# SAMV71_Xplained_Ultra_Power_Converter.net
KiCad netlist of a schematic drawn in Altium Designer
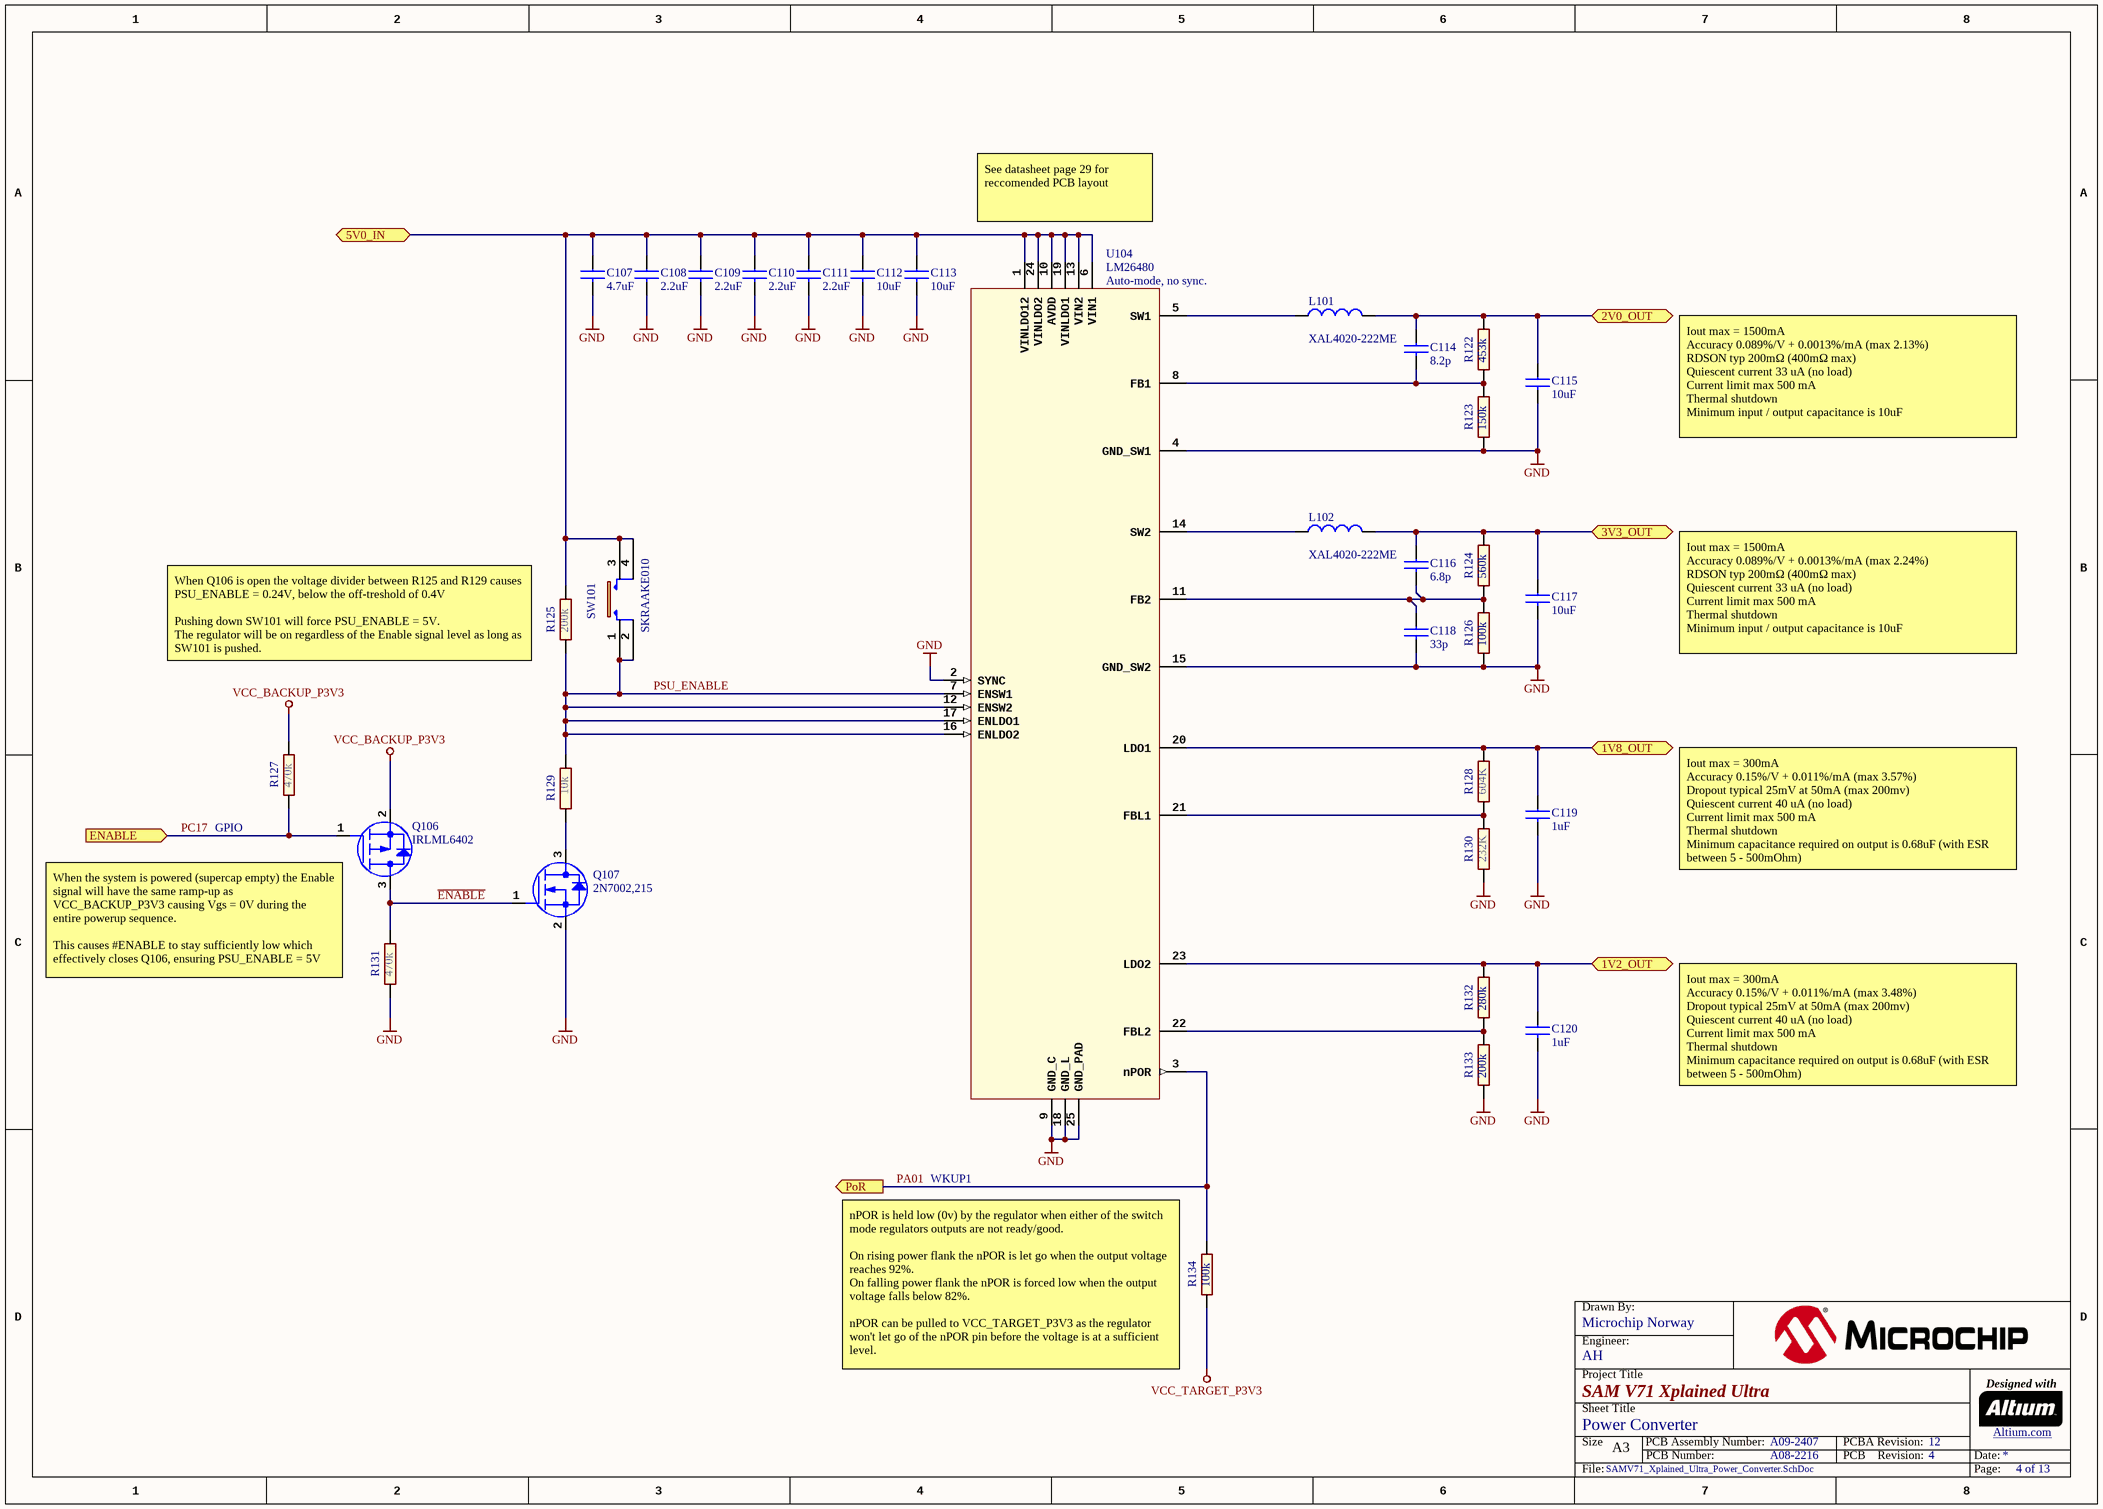
[diagram p0: SAMV71_Xplained_Ultra_Power_Converter.SchDoc]

(export (version "E")
  (design (tool "Eeschema 10.0.6"))
  (components
    (comp (ref "C107")
      (value "4.7uF")
      (footprint "AP1-00039")
      (description "Ceramic capacitor, SMD 0603, X5R, 10V, 10% (de31036)")
      (fields (field (name "TOLERANCE") "10%") (field (name "MANUFACTURER") "WALSIN Technology Corporation"))
      (libsource (lib "AltiumDbLib") (part "CAP-NONPOL"))
    )
    (comp (ref "C108")
      (value "2.2uF")
      (footprint "AP1-00053")
      (description "Ceramic capacitor, SMD 0402, X5R, 6.3V, +/-20%")
      (fields (field (name "TOLERANCE") "Â±20%") (field (name "MANUFACTURER") "Kemet"))
      (libsource (lib "AltiumDbLib") (part "CAP-NONPOL"))
    )
    (comp (ref "C109")
      (value "2.2uF")
      (footprint "AP1-00053")
      (description "Ceramic capacitor, SMD 0402, X5R, 6.3V, +/-20%")
      (fields (field (name "TOLERANCE") "Â±20%") (field (name "MANUFACTURER") "Kemet"))
      (libsource (lib "AltiumDbLib") (part "CAP-NONPOL"))
    )
    (comp (ref "C110")
      (value "2.2uF")
      (footprint "AP1-00053")
      (description "Ceramic capacitor, SMD 0402, X5R, 6.3V, +/-20%")
      (fields (field (name "TOLERANCE") "Â±20%") (field (name "MANUFACTURER") "Kemet"))
      (libsource (lib "AltiumDbLib") (part "CAP-NONPOL"))
    )
    (comp (ref "C111")
      (value "2.2uF")
      (footprint "AP1-00053")
      (description "Ceramic capacitor, SMD 0402, X5R, 6.3V, +/-20%")
      (fields (field (name "TOLERANCE") "Â±20%") (field (name "MANUFACTURER") "Kemet"))
      (libsource (lib "AltiumDbLib") (part "CAP-NONPOL"))
    )
    (comp (ref "C112")
      (value "10uF")
      (footprint "AP1-00041")
      (description "Ceramic capacitor, SMD 0805, X5R, 10V, 10 %, (de19441)")
      (fields (field (name "TOLERANCE") "10%") (field (name "MANUFACTURER") "Murata"))
      (libsource (lib "AltiumDbLib") (part "CAP-NONPOL"))
    )
    (comp (ref "C113")
      (value "10uF")
      (footprint "AP1-00041")
      (description "Ceramic capacitor, SMD 0805, X5R, 10V, 10 %, (de19441)")
      (fields (field (name "TOLERANCE") "10%") (field (name "MANUFACTURER") "Murata"))
      (libsource (lib "AltiumDbLib") (part "CAP-NONPOL"))
    )
    (comp (ref "C114")
      (value "8.2p")
      (footprint "AP1-00053")
      (description "Ceramic capacitor, SMD 0402, NP0, 50V, +/-5%")
      (fields (field (name "TOLERANCE") "50V, +/-5%") (field (name "MANUFACTURER") "YAGEO CORP"))
      (libsource (lib "AltiumDbLib") (part "CAP-NONPOL"))
    )
    (comp (ref "C115")
      (value "10uF")
      (footprint "AP1-00041")
      (description "Ceramic capacitor, SMD 0805, X5R, 10V, 10 %, (de19441)")
      (fields (field (name "TOLERANCE") "10%") (field (name "MANUFACTURER") "Murata"))
      (libsource (lib "AltiumDbLib") (part "CAP-NONPOL"))
    )
    (comp (ref "C116")
      (value "6.8p")
      (footprint "AP1-00053")
      (description "Ceramic capacitor, SMD 0402, NP0, 50V, +/-5%")
      (fields (field (name "TOLERANCE") "50V, +/-5%") (field (name "MANUFACTURER") "YAGEO CORP"))
      (libsource (lib "AltiumDbLib") (part "CAP-NONPOL"))
    )
    (comp (ref "C117")
      (value "10uF")
      (footprint "AP1-00041")
      (description "Ceramic capacitor, SMD 0805, X5R, 10V, 10 %, (de19441)")
      (fields (field (name "TOLERANCE") "10%") (field (name "MANUFACTURER") "Murata"))
      (libsource (lib "AltiumDbLib") (part "CAP-NONPOL"))
    )
    (comp (ref "C118")
      (value "33p")
      (footprint "AP1-00053")
      (description "Ceramic capacitor, SMD 0402, NP0, 50V, +/-5%")
      (fields (field (name "TOLERANCE") "50V, +/-5%") (field (name "MANUFACTURER") "Murata"))
      (libsource (lib "AltiumDbLib") (part "CAP-NONPOL"))
    )
    (comp (ref "C119")
      (value "1uF")
      (footprint "AP1-00053")
      (description "Ceramic capacitor, SMD 0402, X5R, 10V, ±10 %")
      (fields (field (name "MANUFACTURER") "AVX") (field (name "MPN") "0402ZD105KAT2A"))
      (libsource (lib "AltiumDbLib") (part "CAP-NONPOL"))
    )
    (comp (ref "C120")
      (value "1uF")
      (footprint "AP1-00053")
      (description "Ceramic capacitor, SMD 0402, X5R, 10V, ±10 %")
      (fields (field (name "MANUFACTURER") "AVX") (field (name "MPN") "0402ZD105KAT2A"))
      (libsource (lib "AltiumDbLib") (part "CAP-NONPOL"))
    )
    (comp (ref "L101")
      (value "XAL4020-222ME")
      (footprint "AP3-00119")
      (description "2.2ÂµH Shielded Power Inductor, 4x4x2mm, Isat=5.6A , Irms=4.0A , DCR=35.2mÎ©")
      (fields (field (name "TOLERANCE") "20%") (field (name "MANUFACTURER") "Coilcraft"))
      (libsource (lib "AltiumDbLib") (part "INDUCTOR"))
    )
    (comp (ref "L102")
      (value "XAL4020-222ME")
      (footprint "AP3-00119")
      (description "2.2ÂµH Shielded Power Inductor, 4x4x2mm, Isat=5.6A , Irms=4.0A , DCR=35.2mÎ©")
      (fields (field (name "TOLERANCE") "20%") (field (name "MANUFACTURER") "Coilcraft"))
      (libsource (lib "AltiumDbLib") (part "INDUCTOR"))
    )
    (comp (ref "Q106")
      (value "IRLML6402")
      (footprint "AP5-00002")
      (description "P-ch. MOSFET. -30V, -3.7A continuous,RDS(ON)=0.05Ohm@VGS=-4,5V, RDS(ON)=0.08Ohm@VGS=-2.5V")
      (fields (field (name "MANUFACTURER") "International Rectifier") (field (name "MPN") "IRLML6402PBF"))
      (libsource (lib "AltiumDbLib") (part "MOSFET_P_GSD"))
    )
    (comp (ref "Q107")
      (value "2N7002,215")
      (footprint "AP5-00002")
      (description "N-Channel MOSFET. 60V, 0.300A continuous, 1.2A Peak. RDS(ON) = 3.8Ohm@VGS=4.5V, VGS(th)<2.5V")
      (fields (field (name "MANUFACTURER") "NXP"))
      (libsource (lib "AltiumDbLib") (part "MOSFET_N_GSD"))
    )
    (comp (ref "R122")
      (value "453k")
      (footprint "AP2-00011")
      (description "Thick film resistor, SMD 0402, 1/16W, 1%")
      (fields (field (name "TOLERANCE") "1 %"))
      (libsource (lib "AltiumDbLib") (part "R2"))
    )
    (comp (ref "R123")
      (value "150k")
      (footprint "AP2-00011")
      (description "Thick film resistor, SMD 0402, 1/16W, 1%")
      (fields (field (name "TOLERANCE") "1 %") (field (name "MANUFACTURER") "ASJ"))
      (libsource (lib "AltiumDbLib") (part "R2"))
    )
    (comp (ref "R124")
      (value "560k")
      (footprint "AP2-00011")
      (description "Thick film resistor, SMD 0402, 1/16W, 1%")
      (fields (field (name "TOLERANCE") "1 %"))
      (libsource (lib "AltiumDbLib") (part "R2"))
    )
    (comp (ref "R125")
      (value "200k")
      (footprint "AP2-00011")
      (description "Thick film resistor, SMD 0402, 1/16W, 1%")
      (fields (field (name "TOLERANCE") "1 %") (field (name "MANUFACTURER") "ASJ"))
      (libsource (lib "AltiumDbLib") (part "R2"))
    )
    (comp (ref "R126")
      (value "100k")
      (footprint "AP2-00011")
      (description "Thick film resistor, SMD 0402, 1/16W, 1%")
      (fields (field (name "TOLERANCE") "1 %") (field (name "MANUFACTURER") "ASJ"))
      (libsource (lib "") (part "R2_1"))
    )
    (comp (ref "R127")
      (value "470k")
      (footprint "AP2-00011")
      (description "Thick film resistor, SMD 0402, 1/16W, 1%")
      (fields (field (name "TOLERANCE") "1 %") (field (name "MANUFACTURER") "ASJ"))
      (libsource (lib "AltiumDbLib") (part "R2"))
    )
    (comp (ref "R128")
      (value "604K")
      (footprint "AP2-00011")
      (description "Thick film resistor, SMD 0402, 1/16W, 1%")
      (fields (field (name "TOLERANCE") "1 %"))
      (libsource (lib "AltiumDbLib") (part "R2"))
    )
    (comp (ref "R129")
      (value "10k")
      (footprint "AP2-00011")
      (description "Thick film resistor, SMD 0402, 1/16W, 1%")
      (fields (field (name "TOLERANCE") "1 %") (field (name "MANUFACTURER") "vishay"))
      (libsource (lib "AltiumDbLib") (part "R2"))
    )
    (comp (ref "R130")
      (value "232K")
      (footprint "AP2-00011")
      (description "Thick film resistor, SMD 0402, 1/16W, 1%")
      (fields (field (name "TOLERANCE") "1 %") (field (name "MANUFACTURER") "PHYCOMP"))
      (libsource (lib "AltiumDbLib") (part "R2"))
    )
    (comp (ref "R131")
      (value "470k")
      (footprint "AP2-00011")
      (description "Thick film resistor, SMD 0402, 1/16W, 1%")
      (fields (field (name "TOLERANCE") "1 %") (field (name "MANUFACTURER") "ASJ"))
      (libsource (lib "AltiumDbLib") (part "R2"))
    )
    (comp (ref "R132")
      (value "280k")
      (footprint "AP2-00011")
      (description "Thick film resistor, SMD 0402, 1/16W, 1%")
      (fields (field (name "TOLERANCE") "1 %"))
      (libsource (lib "AltiumDbLib") (part "R2"))
    )
    (comp (ref "R133")
      (value "200k")
      (footprint "AP2-00011")
      (description "Thick film resistor, SMD 0402, 1/16W, 1%")
      (fields (field (name "TOLERANCE") "1 %") (field (name "MANUFACTURER") "ASJ"))
      (libsource (lib "AltiumDbLib") (part "R2"))
    )
    (comp (ref "R134")
      (value "100k")
      (footprint "AP2-00011")
      (description "Thick film resistor, SMD 0402, 1/16W, 1%")
      (fields (field (name "TOLERANCE") "1 %") (field (name "MANUFACTURER") "ASJ"))
      (libsource (lib "") (part "R2_1"))
    )
    (comp (ref "SW101")
      (value "SKRAAKE010")
      (footprint "AP8-00137")
      (description "6.2x6.2 mm SMD tact switch, same as A08-0091 but less force is needed")
      (fields (field (name "MANUFACTURER") "ALPS"))
      (libsource (lib "AltiumDbLib") (part "PUSHBUTTON1"))
    )
    (comp (ref "U104")
      (value "Auto-mode, no sync.")
      (footprint "AP6-00380")
      (description "Externally Programmable Dual High-Current Step-Down DC/DC and Dual Linear Regulators")
      (fields
        (field (name "ALTIUM_VALUE") "LM26480")
        (field (name "MANUFACTURER") "Texas Instruments")
        (field (name "MPN") "LM26480SQ-AA/NOPB")
      )
      (libsource (lib "AltiumDbLib") (part "LM26480"))
    )
  )
  (nets
    (net (code "1") (name "/1V2_OUT") (class "Default")
      (node (ref "C120") (pin "1") (pinfunction "1_1") (pintype "passive"))
      (node (ref "R132") (pin "2") (pinfunction "2_2") (pintype "passive"))
      (node (ref "U104") (pin "23") (pinfunction "LDO2_23") (pintype "power_in"))
    )
    (net (code "2") (name "/1V8_OUT") (class "Default")
      (node (ref "C119") (pin "1") (pinfunction "1_1") (pintype "passive"))
      (node (ref "R128") (pin "2") (pinfunction "2_2") (pintype "passive"))
      (node (ref "U104") (pin "20") (pinfunction "LDO1_20") (pintype "power_in"))
    )
    (net (code "3") (name "/2V0_OUT") (class "Default")
      (node (ref "C114") (pin "1") (pinfunction "1_1") (pintype "passive"))
      (node (ref "C115") (pin "1") (pinfunction "1_1") (pintype "passive"))
      (node (ref "L101") (pin "2") (pinfunction "2_2") (pintype "passive"))
      (node (ref "R122") (pin "2") (pinfunction "2_2") (pintype "passive"))
    )
    (net (code "4") (name "/3V3_OUT") (class "Default")
      (node (ref "C116") (pin "1") (pinfunction "1_1") (pintype "passive"))
      (node (ref "C117") (pin "1") (pinfunction "1_1") (pintype "passive"))
      (node (ref "L102") (pin "2") (pinfunction "2_2") (pintype "passive"))
      (node (ref "R124") (pin "2") (pinfunction "2_2") (pintype "passive"))
    )
    (net (code "5") (name "/5V0_IN") (class "Default")
      (node (ref "C107") (pin "1") (pinfunction "1_1") (pintype "passive"))
      (node (ref "C108") (pin "1") (pinfunction "1_1") (pintype "passive"))
      (node (ref "C109") (pin "1") (pinfunction "1_1") (pintype "passive"))
      (node (ref "C110") (pin "1") (pinfunction "1_1") (pintype "passive"))
      (node (ref "C111") (pin "1") (pinfunction "1_1") (pintype "passive"))
      (node (ref "C112") (pin "1") (pinfunction "1_1") (pintype "passive"))
      (node (ref "C113") (pin "1") (pinfunction "1_1") (pintype "passive"))
      (node (ref "R125") (pin "2") (pinfunction "2_2") (pintype "passive"))
      (node (ref "SW101") (pin "3") (pinfunction "3_3") (pintype "passive"))
      (node (ref "SW101") (pin "4") (pinfunction "4_4") (pintype "passive"))
      (node (ref "U104") (pin "1") (pinfunction "VINLDO12_1") (pintype "power_in"))
      (node (ref "U104") (pin "10") (pinfunction "AVDD_10") (pintype "power_in"))
      (node (ref "U104") (pin "13") (pinfunction "VIN2_13") (pintype "power_in"))
      (node (ref "U104") (pin "19") (pinfunction "VINLDO1_19") (pintype "power_in"))
      (node (ref "U104") (pin "24") (pinfunction "VINLDO2_24") (pintype "power_in"))
      (node (ref "U104") (pin "6") (pinfunction "VIN1_6") (pintype "power_in"))
    )
    (net (code "6") (name "/PA01") (class "Default")
      (node (ref "R134") (pin "1") (pinfunction "1_1") (pintype "passive"))
      (node (ref "U104") (pin "3") (pinfunction "nPOR_3") (pintype "output"))
    )
    (net (code "7") (name "/PC17") (class "Default")
      (node (ref "Q106") (pin "1") (pinfunction "G_1") (pintype "passive"))
      (node (ref "R127") (pin "1") (pinfunction "1_1") (pintype "passive"))
    )
    (net (code "8") (name "/PSU_ENABLE") (class "Default")
      (node (ref "R125") (pin "1") (pinfunction "1_1") (pintype "passive"))
      (node (ref "R129") (pin "2") (pinfunction "2_2") (pintype "passive"))
      (node (ref "SW101") (pin "1") (pinfunction "1_1") (pintype "passive"))
      (node (ref "SW101") (pin "2") (pinfunction "2_2") (pintype "passive"))
      (node (ref "U104") (pin "12") (pinfunction "ENSW2_12") (pintype "input"))
      (node (ref "U104") (pin "16") (pinfunction "ENLDO2_16") (pintype "input"))
      (node (ref "U104") (pin "17") (pinfunction "ENLDO1_17") (pintype "input"))
      (node (ref "U104") (pin "7") (pinfunction "ENSW1_7") (pintype "input"))
    )
    (net (code "9") (name "/~{ENABLE}") (class "Default")
      (node (ref "Q106") (pin "3") (pinfunction "D_3") (pintype "passive"))
      (node (ref "Q107") (pin "1") (pinfunction "G_1") (pintype "passive"))
      (node (ref "R131") (pin "2") (pinfunction "2_2") (pintype "passive"))
    )
    (net (code "10") (name "GND") (class "Default")
      (node (ref "C107") (pin "2") (pinfunction "2_2") (pintype "passive"))
      (node (ref "C108") (pin "2") (pinfunction "2_2") (pintype "passive"))
      (node (ref "C109") (pin "2") (pinfunction "2_2") (pintype "passive"))
      (node (ref "C110") (pin "2") (pinfunction "2_2") (pintype "passive"))
      (node (ref "C111") (pin "2") (pinfunction "2_2") (pintype "passive"))
      (node (ref "C112") (pin "2") (pinfunction "2_2") (pintype "passive"))
      (node (ref "C113") (pin "2") (pinfunction "2_2") (pintype "passive"))
      (node (ref "C115") (pin "2") (pinfunction "2_2") (pintype "passive"))
      (node (ref "C117") (pin "2") (pinfunction "2_2") (pintype "passive"))
      (node (ref "C118") (pin "2") (pinfunction "2_2") (pintype "passive"))
      (node (ref "C119") (pin "2") (pinfunction "2_2") (pintype "passive"))
      (node (ref "C120") (pin "2") (pinfunction "2_2") (pintype "passive"))
      (node (ref "Q107") (pin "2") (pinfunction "S_2") (pintype "passive"))
      (node (ref "R123") (pin "1") (pinfunction "1_1") (pintype "passive"))
      (node (ref "R126") (pin "2") (pinfunction "2_2") (pintype "passive"))
      (node (ref "R130") (pin "1") (pinfunction "1_1") (pintype "passive"))
      (node (ref "R131") (pin "1") (pinfunction "1_1") (pintype "passive"))
      (node (ref "R133") (pin "1") (pinfunction "1_1") (pintype "passive"))
      (node (ref "U104") (pin "15") (pinfunction "GND_SW2_15") (pintype "power_in"))
      (node (ref "U104") (pin "18") (pinfunction "GND_L_18") (pintype "power_in"))
      (node (ref "U104") (pin "2") (pinfunction "SYNC_2") (pintype "input"))
      (node (ref "U104") (pin "25") (pinfunction "GND_PAD_25") (pintype "passive"))
      (node (ref "U104") (pin "4") (pinfunction "GND_SW1_4") (pintype "power_in"))
      (node (ref "U104") (pin "9") (pinfunction "GND_C_9") (pintype "power_in"))
    )
    (net (code "11") (name "Net-(Q107-D)") (class "Default")
      (node (ref "Q107") (pin "3") (pinfunction "D_3") (pintype "passive"))
      (node (ref "R129") (pin "1") (pinfunction "1_1") (pintype "passive"))
    )
    (net (code "12") (name "Net-(U104-FB1)") (class "Default")
      (node (ref "C114") (pin "2") (pinfunction "2_2") (pintype "passive"))
      (node (ref "R122") (pin "1") (pinfunction "1_1") (pintype "passive"))
      (node (ref "R123") (pin "2") (pinfunction "2_2") (pintype "passive"))
      (node (ref "U104") (pin "8") (pinfunction "FB1_8") (pintype "power_in"))
    )
    (net (code "13") (name "Net-(U104-FB2)") (class "Default")
      (node (ref "C116") (pin "2") (pinfunction "2_2") (pintype "passive"))
      (node (ref "C118") (pin "1") (pinfunction "1_1") (pintype "passive"))
      (node (ref "R124") (pin "1") (pinfunction "1_1") (pintype "passive"))
      (node (ref "R126") (pin "1") (pinfunction "1_1") (pintype "passive"))
      (node (ref "U104") (pin "11") (pinfunction "FB2_11") (pintype "power_in"))
    )
    (net (code "14") (name "Net-(U104-FBL1)") (class "Default")
      (node (ref "R128") (pin "1") (pinfunction "1_1") (pintype "passive"))
      (node (ref "R130") (pin "2") (pinfunction "2_2") (pintype "passive"))
      (node (ref "U104") (pin "21") (pinfunction "FBL1_21") (pintype "power_in"))
    )
    (net (code "15") (name "Net-(U104-FBL2)") (class "Default")
      (node (ref "R132") (pin "1") (pinfunction "1_1") (pintype "passive"))
      (node (ref "R133") (pin "2") (pinfunction "2_2") (pintype "passive"))
      (node (ref "U104") (pin "22") (pinfunction "FBL2_22") (pintype "power_in"))
    )
    (net (code "16") (name "Net-(U104-SW1)") (class "Default")
      (node (ref "L101") (pin "1") (pinfunction "1_1") (pintype "passive"))
      (node (ref "U104") (pin "5") (pinfunction "SW1_5") (pintype "power_in"))
    )
    (net (code "17") (name "Net-(U104-SW2)") (class "Default")
      (node (ref "L102") (pin "1") (pinfunction "1_1") (pintype "passive"))
      (node (ref "U104") (pin "14") (pinfunction "SW2_14") (pintype "power_in"))
    )
    (net (code "18") (name "VCC_BACKUP_P3V3") (class "Default")
      (node (ref "Q106") (pin "2") (pinfunction "S_2") (pintype "passive"))
      (node (ref "R127") (pin "2") (pinfunction "2_2") (pintype "passive"))
    )
    (net (code "19") (name "VCC_TARGET_P3V3") (class "Default")
      (node (ref "R134") (pin "2") (pinfunction "2_2") (pintype "passive"))
    )
  )
)
